# SOT23-8-minimal.net
KiCad netlist of a schematic drawn in EAGLE
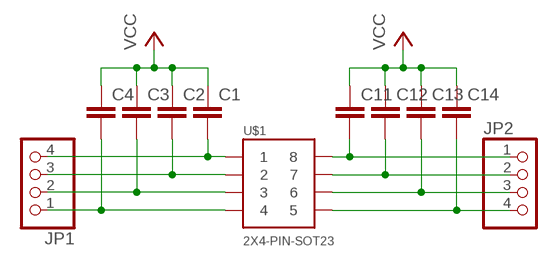
[diagram p0: schematic, sheet 1]

(export (version "E")
  (design (tool "Eeschema 10.0.6"))
  (components
    (comp (ref "C1")
      (value "C-EUC0603")
      (footprint "eagle-import:C0603")
      (libsource (lib "eagle-import") (part "C-EUC0603"))
    )
    (comp (ref "C2")
      (value "C-EUC0603")
      (footprint "eagle-import:C0603")
      (libsource (lib "eagle-import") (part "C-EUC0603"))
    )
    (comp (ref "C3")
      (value "C-EUC0603")
      (footprint "eagle-import:C0603")
      (libsource (lib "eagle-import") (part "C-EUC0603"))
    )
    (comp (ref "C4")
      (value "C-EUC0603")
      (footprint "eagle-import:C0603")
      (libsource (lib "eagle-import") (part "C-EUC0603"))
    )
    (comp (ref "C11")
      (value "C-EUC0603")
      (footprint "eagle-import:C0603")
      (libsource (lib "eagle-import") (part "C-EUC0603"))
    )
    (comp (ref "C12")
      (value "C-EUC0603")
      (footprint "eagle-import:C0603")
      (libsource (lib "eagle-import") (part "C-EUC0603"))
    )
    (comp (ref "C13")
      (value "C-EUC0603")
      (footprint "eagle-import:C0603")
      (libsource (lib "eagle-import") (part "C-EUC0603"))
    )
    (comp (ref "C14")
      (value "C-EUC0603")
      (footprint "eagle-import:C0603")
      (libsource (lib "eagle-import") (part "C-EUC0603"))
    )
    (comp (ref "JP1")
      (value "PINHD-1X4")
      (footprint "eagle-import:1X04")
      (libsource (lib "eagle-import") (part "PINHD-1X4"))
    )
    (comp (ref "JP2")
      (value "PINHD-1X4")
      (footprint "eagle-import:1X04")
      (libsource (lib "eagle-import") (part "PINHD-1X4"))
    )
    (comp (ref "U$1")
      (value "2X4-PIN-SOT23")
      (footprint "eagle-import:SOT23-8")
      (libsource (lib "eagle-import") (part "2X4-PIN-SOT23"))
    )
  )
  (nets
    (net (code "1") (name "Net-(U$1-1)") (class "Default")
      (node (ref "C1") (pin "2") (pinfunction "2_2") (pintype "passive"))
      (node (ref "JP1") (pin "4") (pinfunction "4_4") (pintype "passive"))
      (node (ref "U$1") (pin "P$1") (pinfunction "1_P$1") (pintype "bidirectional"))
    )
    (net (code "2") (name "Net-(U$1-2)") (class "Default")
      (node (ref "C2") (pin "2") (pinfunction "2_2") (pintype "passive"))
      (node (ref "JP1") (pin "3") (pinfunction "3_3") (pintype "passive"))
      (node (ref "U$1") (pin "P$2") (pinfunction "2_P$2") (pintype "bidirectional"))
    )
    (net (code "3") (name "Net-(U$1-3)") (class "Default")
      (node (ref "C3") (pin "2") (pinfunction "2_2") (pintype "passive"))
      (node (ref "JP1") (pin "2") (pinfunction "2_2") (pintype "passive"))
      (node (ref "U$1") (pin "P$3") (pinfunction "3_P$3") (pintype "bidirectional"))
    )
    (net (code "4") (name "Net-(U$1-4)") (class "Default")
      (node (ref "C4") (pin "2") (pinfunction "2_2") (pintype "passive"))
      (node (ref "JP1") (pin "1") (pinfunction "1_1") (pintype "passive"))
      (node (ref "U$1") (pin "P$4") (pinfunction "4_P$4") (pintype "bidirectional"))
    )
    (net (code "5") (name "Net-(U$1-5)") (class "Default")
      (node (ref "C14") (pin "2") (pinfunction "2_2") (pintype "passive"))
      (node (ref "JP2") (pin "4") (pinfunction "4_4") (pintype "passive"))
      (node (ref "U$1") (pin "P$5") (pinfunction "5_P$5") (pintype "bidirectional"))
    )
    (net (code "6") (name "Net-(U$1-6)") (class "Default")
      (node (ref "C13") (pin "2") (pinfunction "2_2") (pintype "passive"))
      (node (ref "JP2") (pin "3") (pinfunction "3_3") (pintype "passive"))
      (node (ref "U$1") (pin "P$6") (pinfunction "6_P$6") (pintype "bidirectional"))
    )
    (net (code "7") (name "Net-(U$1-7)") (class "Default")
      (node (ref "C12") (pin "2") (pinfunction "2_2") (pintype "passive"))
      (node (ref "JP2") (pin "2") (pinfunction "2_2") (pintype "passive"))
      (node (ref "U$1") (pin "P$7") (pinfunction "7_P$7") (pintype "bidirectional"))
    )
    (net (code "8") (name "Net-(U$1-8)") (class "Default")
      (node (ref "C11") (pin "2") (pinfunction "2_2") (pintype "passive"))
      (node (ref "JP2") (pin "1") (pinfunction "1_1") (pintype "passive"))
      (node (ref "U$1") (pin "P$8") (pinfunction "8_P$8") (pintype "bidirectional"))
    )
    (net (code "9") (name "VCC") (class "Default")
      (node (ref "C1") (pin "1") (pinfunction "1_1") (pintype "passive"))
      (node (ref "C11") (pin "1") (pinfunction "1_1") (pintype "passive"))
      (node (ref "C12") (pin "1") (pinfunction "1_1") (pintype "passive"))
      (node (ref "C13") (pin "1") (pinfunction "1_1") (pintype "passive"))
      (node (ref "C14") (pin "1") (pinfunction "1_1") (pintype "passive"))
      (node (ref "C2") (pin "1") (pinfunction "1_1") (pintype "passive"))
      (node (ref "C3") (pin "1") (pinfunction "1_1") (pintype "passive"))
      (node (ref "C4") (pin "1") (pinfunction "1_1") (pintype "passive"))
    )
  )
)
